# ProximitySensor.net
KiCad netlist of a schematic drawn in EAGLE
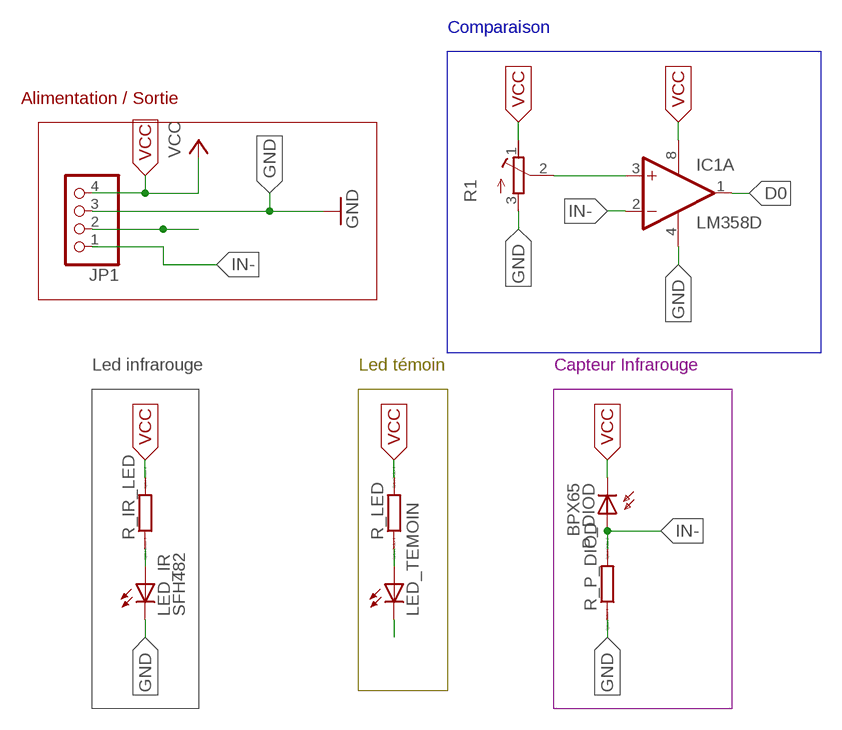
[diagram p0: schematic, sheet 1]

(export (version "E")
  (design (tool "Eeschema 10.0.6"))
  (components
    (comp (ref "IC1")
      (value "LM358D")
      (footprint "eagle-import:SO08")
      (libsource (lib "eagle-import") (part "LM358D"))
    )
    (comp (ref "JP1")
      (value "PINHD-1X4M")
      (footprint "eagle-import:1X04M")
      (libsource (lib "eagle-import") (part "PINHD-1X4M"))
    )
    (comp (ref "LED_IR")
      (value "SFH482")
      (footprint "eagle-import:SFH482")
      (libsource (lib "eagle-import") (part "SFH482"))
    )
    (comp (ref "LED_TEMOIN")
      (value "LEDSMT1206")
      (footprint "eagle-import:1206")
      (libsource (lib "eagle-import") (part "LEDSMT1206"))
    )
    (comp (ref "P_DIOD")
      (value "BPX65")
      (footprint "eagle-import:BPX65")
      (fields (field (name "MPN") "BPX65."))
      (libsource (lib "eagle-import") (part "BPX65"))
    )
    (comp (ref "R1")
      (value "R-TRIMMT93YA")
      (footprint "eagle-import:RTRIMT93YA")
      (libsource (lib "eagle-import") (part "R-TRIMMT93YA"))
    )
    (comp (ref "R_IR_LED")
      (value "RR1206")
      (footprint "eagle-import:R1206")
      (libsource (lib "eagle-import") (part "RR1206"))
    )
    (comp (ref "R_LED")
      (value "RR1206")
      (footprint "eagle-import:R1206")
      (libsource (lib "eagle-import") (part "RR1206"))
    )
    (comp (ref "R_P_DIOD")
      (value "RR1206")
      (footprint "eagle-import:R1206")
      (libsource (lib "eagle-import") (part "RR1206"))
    )
  )
  (nets
    (net (code "1") (name "D0") (class "Default")
      (node (ref "IC1") (pin "1") (pinfunction "OUT_1") (pintype "output"))
      (node (ref "JP1") (pin "2") (pinfunction "2_2") (pintype "passive"))
      (node (ref "LED_TEMOIN") (pin "C") (pinfunction "C_C") (pintype "passive"))
    )
    (net (code "2") (name "GND") (class "Default")
      (node (ref "IC1") (pin "4") (pinfunction "V-_4") (pintype "power_in"))
      (node (ref "JP1") (pin "3") (pinfunction "3_3") (pintype "passive"))
      (node (ref "LED_IR") (pin "K") (pinfunction "C_K") (pintype "passive"))
      (node (ref "R1") (pin "3") (pinfunction "A_3") (pintype "passive"))
      (node (ref "R_P_DIOD") (pin "1") (pinfunction "1_1") (pintype "passive"))
    )
    (net (code "3") (name "IN-") (class "Default")
      (node (ref "IC1") (pin "2") (pinfunction "-IN_2") (pintype "input"))
      (node (ref "JP1") (pin "1") (pinfunction "1_1") (pintype "passive"))
      (node (ref "P_DIOD") (pin "A") (pinfunction "A_A") (pintype "passive"))
      (node (ref "R_P_DIOD") (pin "2") (pinfunction "2_2") (pintype "passive"))
    )
    (net (code "4") (name "Net-(IC1A-+IN)") (class "Default")
      (node (ref "IC1") (pin "3") (pinfunction "+IN_3") (pintype "input"))
      (node (ref "R1") (pin "2") (pinfunction "S_2") (pintype "passive"))
    )
    (net (code "5") (name "Net-(LED_IR-PadA)") (class "Default")
      (node (ref "LED_IR") (pin "A") (pinfunction "A_A") (pintype "passive"))
      (node (ref "R_IR_LED") (pin "1") (pinfunction "1_1") (pintype "passive"))
    )
    (net (code "6") (name "Net-(LED_TEMOIN-PadA)") (class "Default")
      (node (ref "LED_TEMOIN") (pin "A") (pinfunction "A_A") (pintype "passive"))
      (node (ref "R_LED") (pin "1") (pinfunction "1_1") (pintype "passive"))
    )
    (net (code "7") (name "VCC") (class "Default")
      (node (ref "IC1") (pin "8") (pinfunction "V+_8") (pintype "power_in"))
      (node (ref "JP1") (pin "4") (pinfunction "4_4") (pintype "passive"))
      (node (ref "P_DIOD") (pin "K") (pinfunction "C_K") (pintype "passive"))
      (node (ref "R1") (pin "1") (pinfunction "E_1") (pintype "passive"))
      (node (ref "R_IR_LED") (pin "2") (pinfunction "2_2") (pintype "passive"))
      (node (ref "R_LED") (pin "2") (pinfunction "2_2") (pintype "passive"))
    )
  )
)
